# Joystick_Rev_J.net
KiCad netlist of a schematic drawn in EAGLE
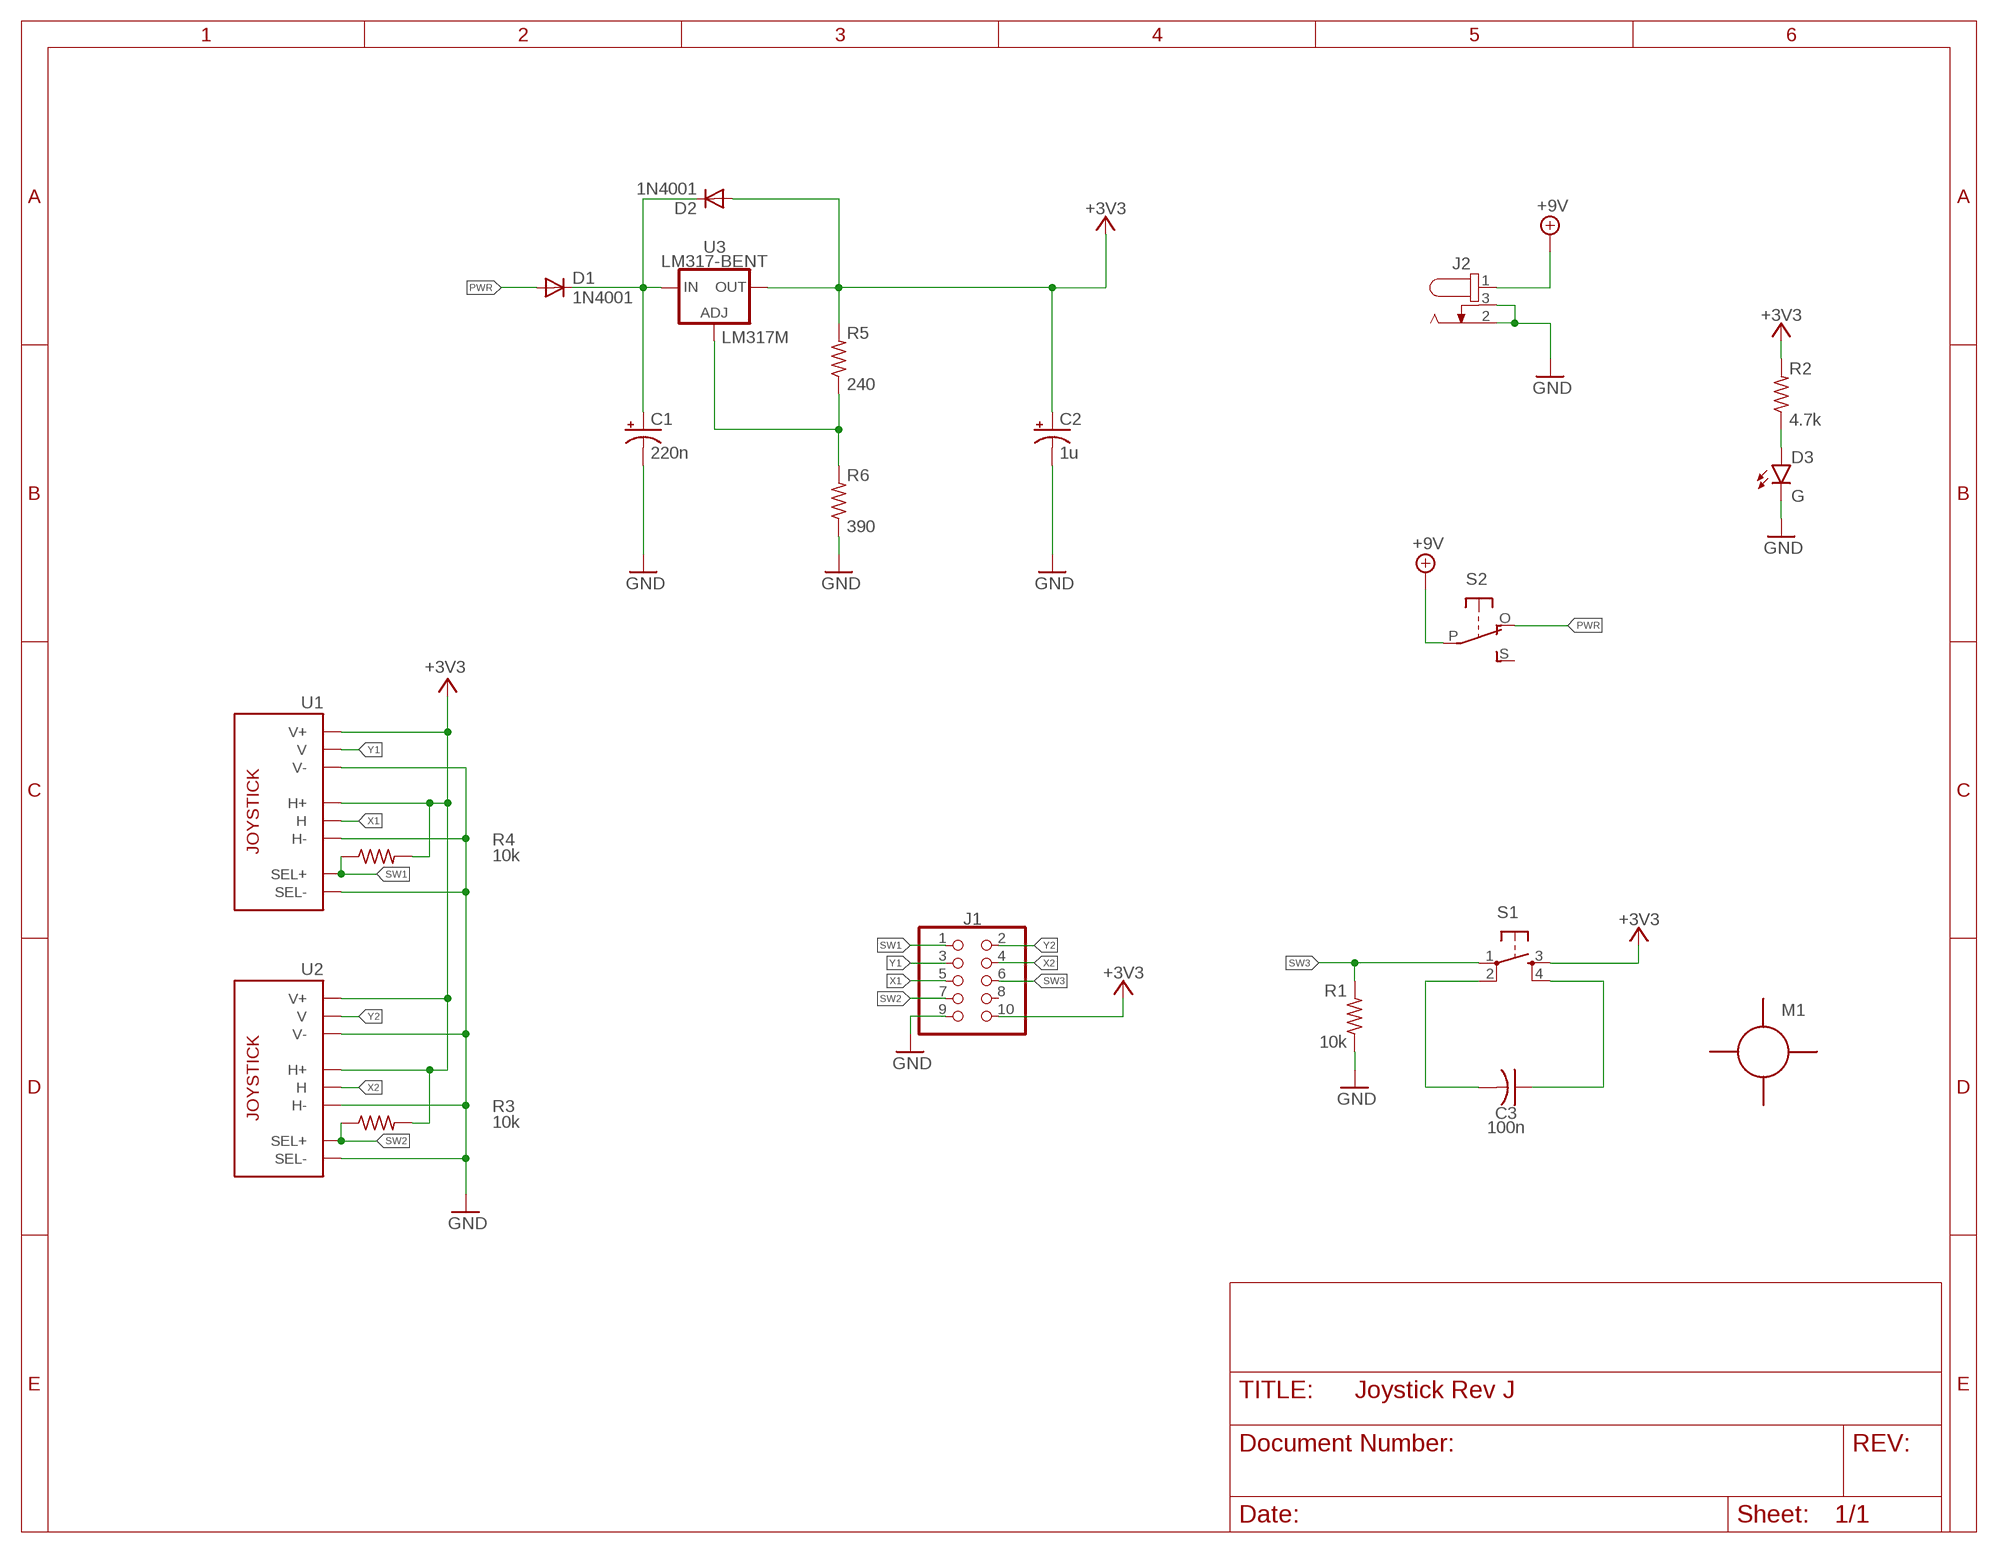
[diagram p0: schematic, sheet 1]

(export (version "E")
  (design (tool "Eeschema 10.0.6"))
  (components
    (comp (ref "C1")
      (value "220n")
      (footprint "eagle-import:E2-4")
      (libsource (lib "eagle-import") (part "ELECTROLYTIC-CAPACITOR2-4"))
    )
    (comp (ref "C2")
      (value "1u")
      (footprint "eagle-import:E2-4")
      (libsource (lib "eagle-import") (part "ELECTROLYTIC-CAPACITOR2-4"))
    )
    (comp (ref "C3")
      (value "100n")
      (footprint "eagle-import:C050-024X044")
      (libsource (lib "eagle-import") (part "THT-CER-CAPACITOR"))
    )
    (comp (ref "D1")
      (value "1N4001")
      (footprint "eagle-import:DO41-10")
      (libsource (lib "eagle-import") (part "1N4000"))
    )
    (comp (ref "D2")
      (value "1N4001")
      (footprint "eagle-import:DO41-10")
      (libsource (lib "eagle-import") (part "1N4000"))
    )
    (comp (ref "D3")
      (value "G")
      (footprint "eagle-import:LED5MM")
      (libsource (lib "eagle-import") (part "LED"))
    )
    (comp (ref "J1")
      (value "RIBBON-2X5")
      (footprint "eagle-import:057-010-1")
      (libsource (lib "eagle-import") (part "RIBBON-2X5"))
    )
    (comp (ref "J2")
      (value "694106301002")
      (footprint "eagle-import:694106301002")
      (libsource (lib "eagle-import") (part "694106301002"))
    )
    (comp (ref "M1")
      (value "9V-HOLDERM2.5")
      (footprint "eagle-import:9V-HOLDER-M2.5")
      (libsource (lib "eagle-import") (part "9V-HOLDERM2.5"))
    )
    (comp (ref "R1")
      (value "10k")
      (footprint "eagle-import:0207_10")
      (libsource (lib "eagle-import") (part "RESISTOR"))
    )
    (comp (ref "R2")
      (value "4.7k")
      (footprint "eagle-import:0207_10")
      (libsource (lib "eagle-import") (part "RESISTOR"))
    )
    (comp (ref "R3")
      (value "10k")
      (footprint "eagle-import:0207_10")
      (libsource (lib "eagle-import") (part "RESISTOR"))
    )
    (comp (ref "R4")
      (value "10k")
      (footprint "eagle-import:0207_10")
      (libsource (lib "eagle-import") (part "RESISTOR"))
    )
    (comp (ref "R5")
      (value "240")
      (footprint "eagle-import:0207_10")
      (libsource (lib "eagle-import") (part "RESISTOR"))
    )
    (comp (ref "R6")
      (value "390")
      (footprint "eagle-import:0207_10")
      (libsource (lib "eagle-import") (part "RESISTOR"))
    )
    (comp (ref "S1")
      (value "TACTILE-BUTTON40XX")
      (footprint "eagle-import:B3F-40XX")
      (fields (field (name "SPICEPREFIX") "S"))
      (libsource (lib "eagle-import") (part "TACTILE-BUTTON40XX"))
    )
    (comp (ref "S2")
      (value "SLIDE-SWITCHSIDE")
      (footprint "eagle-import:EG1270-90")
      (libsource (lib "eagle-import") (part "SLIDE-SWITCHSIDE"))
    )
    (comp (ref "U1")
      (value "JOYSTICK")
      (footprint "eagle-import:JOYSTICK")
      (libsource (lib "eagle-import") (part "JOYSTICK"))
    )
    (comp (ref "U2")
      (value "JOYSTICK")
      (footprint "eagle-import:JOYSTICK")
      (libsource (lib "eagle-import") (part "JOYSTICK"))
    )
    (comp (ref "U3")
      (value "LM317-BENT")
      (footprint "eagle-import:T03B")
      (fields (field (name "PARTNUMBER") "LM317M"))
      (libsource (lib "eagle-import") (part "LM317BENT"))
    )
  )
  (nets
    (net (code "1") (name "+3V3") (class "Default")
      (node (ref "C2") (pin "+") (pinfunction "+_+") (pintype "passive"))
      (node (ref "D2") (pin "A") (pinfunction "A_A") (pintype "passive"))
      (node (ref "J1") (pin "10") (pinfunction "10_10") (pintype "passive"))
      (node (ref "R2") (pin "2") (pinfunction "2_2") (pintype "passive"))
      (node (ref "R3") (pin "2") (pinfunction "2_2") (pintype "passive"))
      (node (ref "R4") (pin "2") (pinfunction "2_2") (pintype "passive"))
      (node (ref "R5") (pin "2") (pinfunction "2_2") (pintype "passive"))
      (node (ref "S1") (pin "3") (pinfunction "S_3") (pintype "passive"))
      (node (ref "U1") (pin "H1") (pinfunction "H+_H1") (pintype "bidirectional"))
      (node (ref "U1") (pin "V1") (pinfunction "V+_V1") (pintype "bidirectional"))
      (node (ref "U2") (pin "H1") (pinfunction "H+_H1") (pintype "bidirectional"))
      (node (ref "U2") (pin "V1") (pinfunction "V+_V1") (pintype "bidirectional"))
      (node (ref "U3") (pin "2") (pinfunction "OUT_2") (pintype "passive"))
    )
    (net (code "2") (name "+9V") (class "Default")
      (node (ref "J2") (pin "1") (pinfunction "1_1") (pintype "passive"))
      (node (ref "S2") (pin "P") (pinfunction "P_P") (pintype "passive"))
    )
    (net (code "3") (name "GND") (class "Default")
      (node (ref "C1") (pin "-") (pinfunction "-_-") (pintype "passive"))
      (node (ref "C2") (pin "-") (pinfunction "-_-") (pintype "passive"))
      (node (ref "D3") (pin "K") (pinfunction "C_K") (pintype "passive"))
      (node (ref "J1") (pin "9") (pinfunction "9_9") (pintype "passive"))
      (node (ref "J2") (pin "2") (pinfunction "2_2") (pintype "passive"))
      (node (ref "J2") (pin "3") (pinfunction "3_3") (pintype "passive"))
      (node (ref "R1") (pin "1") (pinfunction "1_1") (pintype "passive"))
      (node (ref "R6") (pin "1") (pinfunction "1_1") (pintype "passive"))
      (node (ref "U1") (pin "B2A") (pinfunction "SEL-_B2A") (pintype "bidirectional"))
      (node (ref "U1") (pin "H3") (pinfunction "H-_H3") (pintype "bidirectional"))
      (node (ref "U1") (pin "V3") (pinfunction "V-_V3") (pintype "bidirectional"))
      (node (ref "U2") (pin "B2A") (pinfunction "SEL-_B2A") (pintype "bidirectional"))
      (node (ref "U2") (pin "H3") (pinfunction "H-_H3") (pintype "bidirectional"))
      (node (ref "U2") (pin "V3") (pinfunction "V-_V3") (pintype "bidirectional"))
    )
    (net (code "4") (name "Net-(D3-PadA)") (class "Default")
      (node (ref "D3") (pin "A") (pinfunction "A_A") (pintype "passive"))
      (node (ref "R2") (pin "1") (pinfunction "1_1") (pintype "passive"))
    )
    (net (code "5") (name "Net-(S1-P1)") (class "Default")
      (node (ref "C3") (pin "2") (pinfunction "2_2") (pintype "passive"))
      (node (ref "S1") (pin "2") (pinfunction "P1_2") (pintype "passive"))
    )
    (net (code "6") (name "Net-(S1-S1)") (class "Default")
      (node (ref "C3") (pin "1") (pinfunction "1_1") (pintype "passive"))
      (node (ref "S1") (pin "4") (pinfunction "S1_4") (pintype "passive"))
    )
    (net (code "7") (name "Net-(U3-ADJ)") (class "Default")
      (node (ref "R5") (pin "1") (pinfunction "1_1") (pintype "passive"))
      (node (ref "R6") (pin "2") (pinfunction "2_2") (pintype "passive"))
      (node (ref "U3") (pin "1") (pinfunction "ADJ_1") (pintype "input"))
    )
    (net (code "8") (name "Net-(U3-IN)") (class "Default")
      (node (ref "C1") (pin "+") (pinfunction "+_+") (pintype "passive"))
      (node (ref "D1") (pin "C") (pinfunction "C_C") (pintype "passive"))
      (node (ref "D2") (pin "C") (pinfunction "C_C") (pintype "passive"))
      (node (ref "U3") (pin "3") (pinfunction "IN_3") (pintype "input"))
    )
    (net (code "9") (name "PWR") (class "Default")
      (node (ref "D1") (pin "A") (pinfunction "A_A") (pintype "passive"))
      (node (ref "S2") (pin "O") (pinfunction "O_O") (pintype "passive"))
    )
    (net (code "10") (name "SW1") (class "Default")
      (node (ref "J1") (pin "1") (pinfunction "1_1") (pintype "passive"))
      (node (ref "R4") (pin "1") (pinfunction "1_1") (pintype "passive"))
      (node (ref "U1") (pin "B1A") (pinfunction "SEL+_B1A") (pintype "bidirectional"))
    )
    (net (code "11") (name "SW2") (class "Default")
      (node (ref "J1") (pin "7") (pinfunction "7_7") (pintype "passive"))
      (node (ref "R3") (pin "1") (pinfunction "1_1") (pintype "passive"))
      (node (ref "U2") (pin "B1A") (pinfunction "SEL+_B1A") (pintype "bidirectional"))
    )
    (net (code "12") (name "SW3") (class "Default")
      (node (ref "J1") (pin "6") (pinfunction "6_6") (pintype "passive"))
      (node (ref "R1") (pin "2") (pinfunction "2_2") (pintype "passive"))
      (node (ref "S1") (pin "1") (pinfunction "P_1") (pintype "passive"))
    )
    (net (code "13") (name "X1") (class "Default")
      (node (ref "J1") (pin "5") (pinfunction "5_5") (pintype "passive"))
      (node (ref "U1") (pin "H2") (pinfunction "H_H2") (pintype "bidirectional"))
    )
    (net (code "14") (name "X2") (class "Default")
      (node (ref "J1") (pin "4") (pinfunction "4_4") (pintype "passive"))
      (node (ref "U2") (pin "H2") (pinfunction "H_H2") (pintype "bidirectional"))
    )
    (net (code "15") (name "Y1") (class "Default")
      (node (ref "J1") (pin "3") (pinfunction "3_3") (pintype "passive"))
      (node (ref "U1") (pin "V2") (pinfunction "V_V2") (pintype "bidirectional"))
    )
    (net (code "16") (name "Y2") (class "Default")
      (node (ref "J1") (pin "2") (pinfunction "2_2") (pintype "passive"))
      (node (ref "U2") (pin "V2") (pinfunction "V_V2") (pintype "bidirectional"))
    )
    (net (code "17") (name "unconnected-(J1-Pad8)") (class "Default")
      (node (ref "J1") (pin "8") (pinfunction "8_8") (pintype "passive"))
    )
    (net (code "18") (name "unconnected-(S2-PadS)") (class "Default")
      (node (ref "S2") (pin "S") (pinfunction "S_S") (pintype "passive"))
    )
  )
)
